# Connectors.net
KiCad netlist of a schematic drawn in Altium Designer
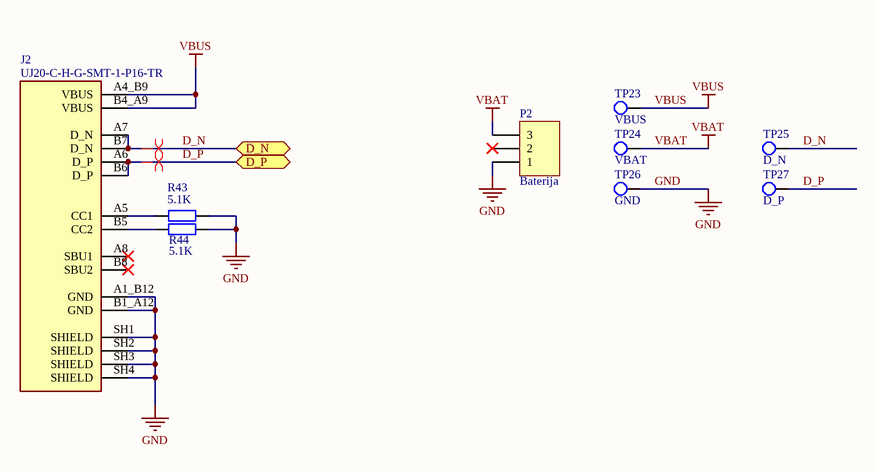
[diagram p0: Connectors.SchDoc]

(export (version "E")
  (design (tool "Eeschema 10.0.6"))
  (components
    (comp (ref "J2")
      (value "UJ20-C-H-G-SMT-1-P16-TR")
      (footprint "SAMESKY_UJ20-C-H-G-SMT-1-P16-TR")
      (fields (field (name "MF") "Same Sky"))
      (libsource (lib "Schematic_library") (part "UJ20-C-H-G-SMT-1-P16-TR"))
    )
    (comp (ref "P2")
      (value "Baterija")
      (footprint "S3B-XH-A-1(LF)(SN)")
      (description "S3B-XH-A-1(LF)(SN)")
      (fields (field (name "PUBLISHER") "Altium Limited"))
      (libsource (lib "Miscellaneous Connectors") (part "Header 3"))
    )
    (comp (ref "R43")
      (value "5.1K")
      (footprint "SMD-0402-RES")
      (description "Resistor")
      (fields (field (name "PUBLISHER") "Altium Limited"))
      (libsource (lib "Miscellaneous Devices") (part "Res2"))
    )
    (comp (ref "R44")
      (value "5.1K")
      (footprint "SMD-0402-RES")
      (description "Resistor")
      (fields (field (name "PUBLISHER") "Altium Limited"))
      (libsource (lib "Miscellaneous Devices") (part "Res2"))
    )
    (comp (ref "TP23")
      (value "VBUS")
      (footprint "testpoint 1 mm")
      (libsource (lib "Schematic_library") (part "testpoint"))
    )
    (comp (ref "TP24")
      (value "VBAT")
      (footprint "testpoint 1 mm")
      (libsource (lib "Schematic_library") (part "testpoint"))
    )
    (comp (ref "TP25")
      (value "D_N")
      (footprint "testpoint 1 mm")
      (libsource (lib "Schematic_library") (part "testpoint"))
    )
    (comp (ref "TP26")
      (value "GND")
      (footprint "testpoint 1 mm")
      (libsource (lib "Schematic_library") (part "testpoint"))
    )
    (comp (ref "TP27")
      (value "D_P")
      (footprint "testpoint 1 mm")
      (libsource (lib "Schematic_library") (part "testpoint"))
    )
  )
  (nets
    (net (code "1") (name "/D_N") (class "Default")
      (node (ref "J2") (pin "A7") (pinfunction "D_N_A7") (pintype "passive"))
      (node (ref "J2") (pin "B7") (pinfunction "D_N_B7") (pintype "passive"))
      (node (ref "TP25") (pin "1") (pinfunction "1_1") (pintype "passive"))
    )
    (net (code "2") (name "/D_P") (class "Default")
      (node (ref "J2") (pin "A6") (pinfunction "D_P_A6") (pintype "passive"))
      (node (ref "J2") (pin "B6") (pinfunction "D_P_B6") (pintype "passive"))
      (node (ref "TP27") (pin "1") (pinfunction "1_1") (pintype "passive"))
    )
    (net (code "3") (name "GND") (class "Default")
      (node (ref "J2") (pin "A1_B12") (pinfunction "GND_A1_B12") (pintype "passive"))
      (node (ref "J2") (pin "B1_A12") (pinfunction "GND_B1_A12") (pintype "passive"))
      (node (ref "J2") (pin "SH1") (pinfunction "SHIELD_SH1") (pintype "passive"))
      (node (ref "J2") (pin "SH2") (pinfunction "SHIELD_SH2") (pintype "passive"))
      (node (ref "J2") (pin "SH3") (pinfunction "SHIELD_SH3") (pintype "passive"))
      (node (ref "J2") (pin "SH4") (pinfunction "SHIELD_SH4") (pintype "passive"))
      (node (ref "P2") (pin "1") (pinfunction "1_1") (pintype "passive"))
      (node (ref "R43") (pin "1") (pinfunction "1_1") (pintype "passive"))
      (node (ref "R44") (pin "1") (pinfunction "1_1") (pintype "passive"))
      (node (ref "TP26") (pin "1") (pinfunction "1_1") (pintype "passive"))
    )
    (net (code "4") (name "Net-(J2-CC1)") (class "Default")
      (node (ref "J2") (pin "A5") (pinfunction "CC1_A5") (pintype "passive"))
      (node (ref "R43") (pin "2") (pinfunction "2_2") (pintype "passive"))
    )
    (net (code "5") (name "Net-(J2-CC2)") (class "Default")
      (node (ref "J2") (pin "B5") (pinfunction "CC2_B5") (pintype "passive"))
      (node (ref "R44") (pin "2") (pinfunction "2_2") (pintype "passive"))
    )
    (net (code "6") (name "VBAT") (class "Default")
      (node (ref "P2") (pin "3") (pinfunction "3_3") (pintype "passive"))
      (node (ref "TP24") (pin "1") (pinfunction "1_1") (pintype "passive"))
    )
    (net (code "7") (name "VBUS") (class "Default")
      (node (ref "J2") (pin "A4_B9") (pinfunction "VBUS_A4_B9") (pintype "passive"))
      (node (ref "J2") (pin "B4_A9") (pinfunction "VBUS_B4_A9") (pintype "passive"))
      (node (ref "TP23") (pin "1") (pinfunction "1_1") (pintype "passive"))
    )
    (net (code "8") (name "unconnected-(J2-SBU1-PadA8)") (class "Default")
      (node (ref "J2") (pin "A8") (pinfunction "SBU1_A8") (pintype "passive+no_connect"))
    )
    (net (code "9") (name "unconnected-(J2-SBU2-PadB8)") (class "Default")
      (node (ref "J2") (pin "B8") (pinfunction "SBU2_B8") (pintype "passive+no_connect"))
    )
    (net (code "10") (name "unconnected-(P2-Pad2)") (class "Default")
      (node (ref "P2") (pin "2") (pinfunction "2_2") (pintype "passive+no_connect"))
    )
  )
)
